# F_BRIDGE.net
KiCad netlist of a schematic drawn in Altium Designer
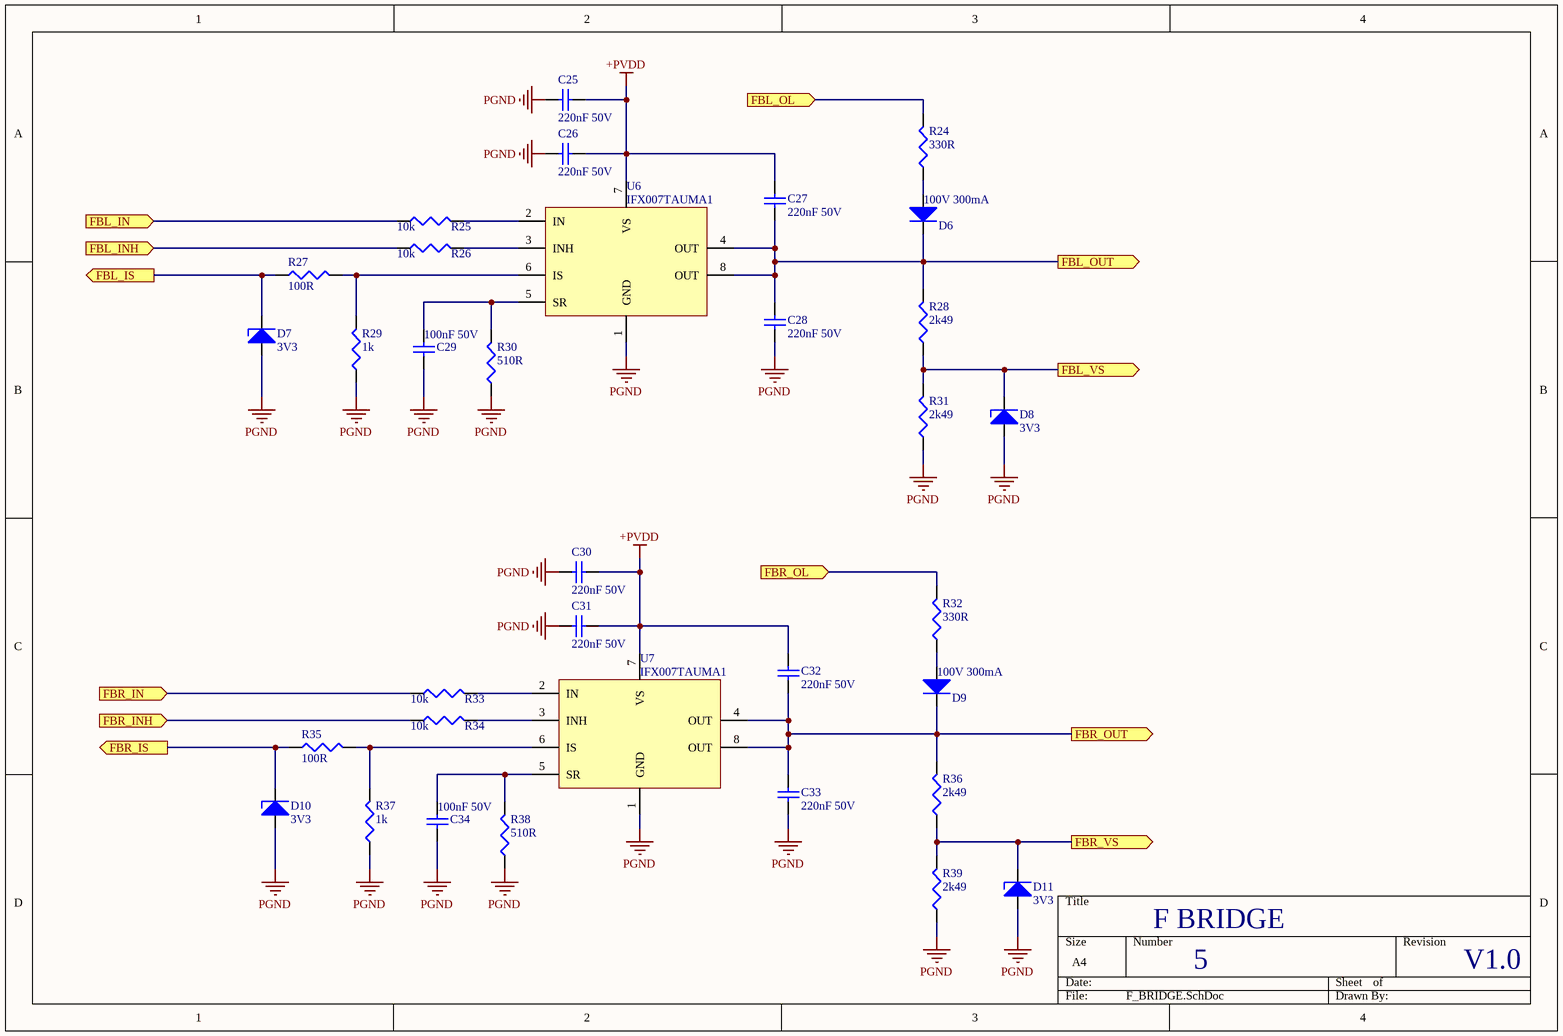
[diagram p0: F_BRIDGE.SchDoc]

(export (version "E")
  (design (tool "Eeschema 10.0.6"))
  (components
    (comp (ref "C25")
      (value "220nF 50V")
      (footprint "CAP1206")
      (description "CAP CER 0.22UF 50V X7R 1206")
      (libsource (lib "SMALL_BCM") (part "CAP1206_220nF"))
    )
    (comp (ref "C26")
      (value "220nF 50V")
      (footprint "CAP1206")
      (description "CAP CER 0.22UF 50V X7R 1206")
      (libsource (lib "SMALL_BCM") (part "CAP1206_220nF"))
    )
    (comp (ref "C27")
      (value "220nF 50V")
      (footprint "CAP1206")
      (description "CAP CER 0.22UF 50V X7R 1206")
      (libsource (lib "SMALL_BCM") (part "CAP1206_220nF"))
    )
    (comp (ref "C28")
      (value "220nF 50V")
      (footprint "CAP1206")
      (description "CAP CER 0.22UF 50V X7R 1206")
      (libsource (lib "SMALL_BCM") (part "CAP1206_220nF"))
    )
    (comp (ref "C29")
      (value "100nF 50V")
      (footprint "CAP0603")
      (description "CAP CER 0.1UF 50V X7R 0603")
      (libsource (lib "SMALL_BCM") (part "CAP0603_100nF"))
    )
    (comp (ref "C30")
      (value "220nF 50V")
      (footprint "CAP1206")
      (description "CAP CER 0.22UF 50V X7R 1206")
      (libsource (lib "SMALL_BCM") (part "CAP1206_220nF"))
    )
    (comp (ref "C31")
      (value "220nF 50V")
      (footprint "CAP1206")
      (description "CAP CER 0.22UF 50V X7R 1206")
      (libsource (lib "SMALL_BCM") (part "CAP1206_220nF"))
    )
    (comp (ref "C32")
      (value "220nF 50V")
      (footprint "CAP1206")
      (description "CAP CER 0.22UF 50V X7R 1206")
      (libsource (lib "SMALL_BCM") (part "CAP1206_220nF"))
    )
    (comp (ref "C33")
      (value "220nF 50V")
      (footprint "CAP1206")
      (description "CAP CER 0.22UF 50V X7R 1206")
      (libsource (lib "SMALL_BCM") (part "CAP1206_220nF"))
    )
    (comp (ref "C34")
      (value "100nF 50V")
      (footprint "CAP0603")
      (description "CAP CER 0.1UF 50V X7R 0603")
      (libsource (lib "SMALL_BCM") (part "CAP0603_100nF"))
    )
    (comp (ref "D6")
      (value "100V 300mA")
      (footprint "SOD123_1N4148W-7-F")
      (description "DIODE GEN PURP 100V 300MA SOD123")
      (libsource (lib "SMALL_BCM") (part "DIODE_1N4148W-7-F"))
    )
    (comp (ref "D7")
      (value "3V3")
      (footprint "SOD323")
      (description "DIODE ZENER 3.3V 300MW SOD323")
      (libsource (lib "SMALL_BCM") (part "ZENER_3V3_MM3Z3V3T1G"))
    )
    (comp (ref "D8")
      (value "3V3")
      (footprint "SOD323")
      (description "DIODE ZENER 3.3V 300MW SOD323")
      (libsource (lib "SMALL_BCM") (part "ZENER_3V3_MM3Z3V3T1G"))
    )
    (comp (ref "D9")
      (value "100V 300mA")
      (footprint "SOD123_1N4148W-7-F")
      (description "DIODE GEN PURP 100V 300MA SOD123")
      (libsource (lib "SMALL_BCM") (part "DIODE_1N4148W-7-F"))
    )
    (comp (ref "D10")
      (value "3V3")
      (footprint "SOD323")
      (description "DIODE ZENER 3.3V 300MW SOD323")
      (libsource (lib "SMALL_BCM") (part "ZENER_3V3_MM3Z3V3T1G"))
    )
    (comp (ref "D11")
      (value "3V3")
      (footprint "SOD323")
      (description "DIODE ZENER 3.3V 300MW SOD323")
      (libsource (lib "SMALL_BCM") (part "ZENER_3V3_MM3Z3V3T1G"))
    )
    (comp (ref "R24")
      (value "330R")
      (footprint "RES0603")
      (description "RES 330 OHM 1% 1/10W 0603")
      (libsource (lib "SMALL_BCM") (part "RES0603_330R"))
    )
    (comp (ref "R25")
      (value "10k")
      (footprint "RES0603")
      (description "RES SMD 10K OHM 5% 1/10W 0603")
      (libsource (lib "SMALL_BCM") (part "RES0603_10k"))
    )
    (comp (ref "R26")
      (value "10k")
      (footprint "RES0603")
      (description "RES SMD 10K OHM 5% 1/10W 0603")
      (libsource (lib "SMALL_BCM") (part "RES0603_10k"))
    )
    (comp (ref "R27")
      (value "100R")
      (footprint "RES0603")
      (description "RES SMD 100R OHM 1% 1/10W 0603")
      (libsource (lib "SMALL_BCM") (part "RES0603_100R"))
    )
    (comp (ref "R28")
      (value "2k49")
      (footprint "RES0603")
      (description "RES 2.49K OHM 1% 1/10W 0603")
      (libsource (lib "SMALL_BCM") (part "RES0603_2k49"))
    )
    (comp (ref "R29")
      (value "1k")
      (footprint "RES0603")
      (description "RES SMD 1K OHM 1% 1/10W 0603")
      (libsource (lib "SMALL_BCM") (part "RES0603_1k"))
    )
    (comp (ref "R30")
      (value "510R")
      (footprint "RES0603")
      (description "RES 510R OHM 1% 1/10W 0603")
      (libsource (lib "SMALL_BCM") (part "RES0603_510R"))
    )
    (comp (ref "R31")
      (value "2k49")
      (footprint "RES0603")
      (description "RES 2.49K OHM 1% 1/10W 0603")
      (libsource (lib "SMALL_BCM") (part "RES0603_2k49"))
    )
    (comp (ref "R32")
      (value "330R")
      (footprint "RES0603")
      (description "RES 330 OHM 1% 1/10W 0603")
      (libsource (lib "SMALL_BCM") (part "RES0603_330R"))
    )
    (comp (ref "R33")
      (value "10k")
      (footprint "RES0603")
      (description "RES SMD 10K OHM 5% 1/10W 0603")
      (libsource (lib "SMALL_BCM") (part "RES0603_10k"))
    )
    (comp (ref "R34")
      (value "10k")
      (footprint "RES0603")
      (description "RES SMD 10K OHM 5% 1/10W 0603")
      (libsource (lib "SMALL_BCM") (part "RES0603_10k"))
    )
    (comp (ref "R35")
      (value "100R")
      (footprint "RES0603")
      (description "RES SMD 100R OHM 1% 1/10W 0603")
      (libsource (lib "SMALL_BCM") (part "RES0603_100R"))
    )
    (comp (ref "R36")
      (value "2k49")
      (footprint "RES0603")
      (description "RES 2.49K OHM 1% 1/10W 0603")
      (libsource (lib "SMALL_BCM") (part "RES0603_2k49"))
    )
    (comp (ref "R37")
      (value "1k")
      (footprint "RES0603")
      (description "RES SMD 1K OHM 1% 1/10W 0603")
      (libsource (lib "SMALL_BCM") (part "RES0603_1k"))
    )
    (comp (ref "R38")
      (value "510R")
      (footprint "RES0603")
      (description "RES 510R OHM 1% 1/10W 0603")
      (libsource (lib "SMALL_BCM") (part "RES0603_510R"))
    )
    (comp (ref "R39")
      (value "2k49")
      (footprint "RES0603")
      (description "RES 2.49K OHM 1% 1/10W 0603")
      (libsource (lib "SMALL_BCM") (part "RES0603_2k49"))
    )
    (comp (ref "U6")
      (value "55A")
      (footprint "TO-263-8")
      (description "IC HALF-BRIDGE DRVR 2 CH TO263")
      (fields (field (name "P/N") "IFX007TAUMA1"))
      (libsource (lib "SMALL_BCM") (part "HB_IFX007TAUMA1"))
    )
    (comp (ref "U7")
      (value "55A")
      (footprint "TO-263-8")
      (description "IC HALF-BRIDGE DRVR 2 CH TO263")
      (fields (field (name "P/N") "IFX007TAUMA1"))
      (libsource (lib "SMALL_BCM") (part "HB_IFX007TAUMA1"))
    )
  )
  (nets
    (net (code "1") (name "+PVDD") (class "Default")
      (node (ref "C25") (pin "2") (pinfunction "2_2") (pintype "passive"))
      (node (ref "C26") (pin "2") (pinfunction "2_2") (pintype "passive"))
      (node (ref "C27") (pin "1") (pinfunction "1_1") (pintype "passive"))
      (node (ref "C30") (pin "2") (pinfunction "2_2") (pintype "passive"))
      (node (ref "C31") (pin "2") (pinfunction "2_2") (pintype "passive"))
      (node (ref "C32") (pin "1") (pinfunction "1_1") (pintype "passive"))
      (node (ref "U6") (pin "7") (pinfunction "VS_7") (pintype "power_in"))
      (node (ref "U7") (pin "7") (pinfunction "VS_7") (pintype "power_in"))
    )
    (net (code "2") (name "/FBL_IN") (class "Default")
      (node (ref "R25") (pin "1") (pinfunction "1_1") (pintype "passive"))
    )
    (net (code "3") (name "/FBL_INH") (class "Default")
      (node (ref "R26") (pin "1") (pinfunction "1_1") (pintype "passive"))
    )
    (net (code "4") (name "/FBL_IS") (class "Default")
      (node (ref "D7") (pin "1") (pinfunction "K_1") (pintype "passive"))
      (node (ref "R27") (pin "1") (pinfunction "1_1") (pintype "passive"))
    )
    (net (code "5") (name "/FBL_OL") (class "Default")
      (node (ref "R24") (pin "2") (pinfunction "2_2") (pintype "passive"))
    )
    (net (code "6") (name "/FBL_OUT") (class "Default")
      (node (ref "C27") (pin "2") (pinfunction "2_2") (pintype "passive"))
      (node (ref "C28") (pin "1") (pinfunction "1_1") (pintype "passive"))
      (node (ref "D6") (pin "2") (pinfunction "K_2") (pintype "passive"))
      (node (ref "R28") (pin "2") (pinfunction "2_2") (pintype "passive"))
      (node (ref "U6") (pin "4") (pinfunction "OUT_4") (pintype "passive"))
      (node (ref "U6") (pin "8") (pinfunction "OUT_8") (pintype "passive"))
    )
    (net (code "7") (name "/FBL_VS") (class "Default")
      (node (ref "D8") (pin "1") (pinfunction "K_1") (pintype "passive"))
      (node (ref "R28") (pin "1") (pinfunction "1_1") (pintype "passive"))
      (node (ref "R31") (pin "2") (pinfunction "2_2") (pintype "passive"))
    )
    (net (code "8") (name "/FBR_IN") (class "Default")
      (node (ref "R33") (pin "1") (pinfunction "1_1") (pintype "passive"))
    )
    (net (code "9") (name "/FBR_INH") (class "Default")
      (node (ref "R34") (pin "1") (pinfunction "1_1") (pintype "passive"))
    )
    (net (code "10") (name "/FBR_IS") (class "Default")
      (node (ref "D10") (pin "1") (pinfunction "K_1") (pintype "passive"))
      (node (ref "R35") (pin "1") (pinfunction "1_1") (pintype "passive"))
    )
    (net (code "11") (name "/FBR_OL") (class "Default")
      (node (ref "R32") (pin "2") (pinfunction "2_2") (pintype "passive"))
    )
    (net (code "12") (name "/FBR_OUT") (class "Default")
      (node (ref "C32") (pin "2") (pinfunction "2_2") (pintype "passive"))
      (node (ref "C33") (pin "1") (pinfunction "1_1") (pintype "passive"))
      (node (ref "D9") (pin "2") (pinfunction "K_2") (pintype "passive"))
      (node (ref "R36") (pin "2") (pinfunction "2_2") (pintype "passive"))
      (node (ref "U7") (pin "4") (pinfunction "OUT_4") (pintype "passive"))
      (node (ref "U7") (pin "8") (pinfunction "OUT_8") (pintype "passive"))
    )
    (net (code "13") (name "/FBR_VS") (class "Default")
      (node (ref "D11") (pin "1") (pinfunction "K_1") (pintype "passive"))
      (node (ref "R36") (pin "1") (pinfunction "1_1") (pintype "passive"))
      (node (ref "R39") (pin "2") (pinfunction "2_2") (pintype "passive"))
    )
    (net (code "14") (name "Net-(D6-A)") (class "Default")
      (node (ref "D6") (pin "1") (pinfunction "A_1") (pintype "passive"))
      (node (ref "R24") (pin "1") (pinfunction "1_1") (pintype "passive"))
    )
    (net (code "15") (name "Net-(D9-A)") (class "Default")
      (node (ref "D9") (pin "1") (pinfunction "A_1") (pintype "passive"))
      (node (ref "R32") (pin "1") (pinfunction "1_1") (pintype "passive"))
    )
    (net (code "16") (name "Net-(U6-IN)") (class "Default")
      (node (ref "R25") (pin "2") (pinfunction "2_2") (pintype "passive"))
      (node (ref "U6") (pin "2") (pinfunction "IN_2") (pintype "passive"))
    )
    (net (code "17") (name "Net-(U6-INH)") (class "Default")
      (node (ref "R26") (pin "2") (pinfunction "2_2") (pintype "passive"))
      (node (ref "U6") (pin "3") (pinfunction "INH_3") (pintype "passive"))
    )
    (net (code "18") (name "Net-(U6-IS)") (class "Default")
      (node (ref "R27") (pin "2") (pinfunction "2_2") (pintype "passive"))
      (node (ref "R29") (pin "2") (pinfunction "2_2") (pintype "passive"))
      (node (ref "U6") (pin "6") (pinfunction "IS_6") (pintype "passive"))
    )
    (net (code "19") (name "Net-(U6-SR)") (class "Default")
      (node (ref "C29") (pin "2") (pinfunction "2_2") (pintype "passive"))
      (node (ref "R30") (pin "2") (pinfunction "2_2") (pintype "passive"))
      (node (ref "U6") (pin "5") (pinfunction "SR_5") (pintype "passive"))
    )
    (net (code "20") (name "Net-(U7-IN)") (class "Default")
      (node (ref "R33") (pin "2") (pinfunction "2_2") (pintype "passive"))
      (node (ref "U7") (pin "2") (pinfunction "IN_2") (pintype "passive"))
    )
    (net (code "21") (name "Net-(U7-INH)") (class "Default")
      (node (ref "R34") (pin "2") (pinfunction "2_2") (pintype "passive"))
      (node (ref "U7") (pin "3") (pinfunction "INH_3") (pintype "passive"))
    )
    (net (code "22") (name "Net-(U7-IS)") (class "Default")
      (node (ref "R35") (pin "2") (pinfunction "2_2") (pintype "passive"))
      (node (ref "R37") (pin "2") (pinfunction "2_2") (pintype "passive"))
      (node (ref "U7") (pin "6") (pinfunction "IS_6") (pintype "passive"))
    )
    (net (code "23") (name "Net-(U7-SR)") (class "Default")
      (node (ref "C34") (pin "2") (pinfunction "2_2") (pintype "passive"))
      (node (ref "R38") (pin "2") (pinfunction "2_2") (pintype "passive"))
      (node (ref "U7") (pin "5") (pinfunction "SR_5") (pintype "passive"))
    )
    (net (code "24") (name "PGND") (class "Default")
      (node (ref "C25") (pin "1") (pinfunction "1_1") (pintype "passive"))
      (node (ref "C26") (pin "1") (pinfunction "1_1") (pintype "passive"))
      (node (ref "C28") (pin "2") (pinfunction "2_2") (pintype "passive"))
      (node (ref "C29") (pin "1") (pinfunction "1_1") (pintype "passive"))
      (node (ref "C30") (pin "1") (pinfunction "1_1") (pintype "passive"))
      (node (ref "C31") (pin "1") (pinfunction "1_1") (pintype "passive"))
      (node (ref "C33") (pin "2") (pinfunction "2_2") (pintype "passive"))
      (node (ref "C34") (pin "1") (pinfunction "1_1") (pintype "passive"))
      (node (ref "D10") (pin "2") (pinfunction "A_2") (pintype "passive"))
      (node (ref "D11") (pin "2") (pinfunction "A_2") (pintype "passive"))
      (node (ref "D7") (pin "2") (pinfunction "A_2") (pintype "passive"))
      (node (ref "D8") (pin "2") (pinfunction "A_2") (pintype "passive"))
      (node (ref "R29") (pin "1") (pinfunction "1_1") (pintype "passive"))
      (node (ref "R30") (pin "1") (pinfunction "1_1") (pintype "passive"))
      (node (ref "R31") (pin "1") (pinfunction "1_1") (pintype "passive"))
      (node (ref "R37") (pin "1") (pinfunction "1_1") (pintype "passive"))
      (node (ref "R38") (pin "1") (pinfunction "1_1") (pintype "passive"))
      (node (ref "R39") (pin "1") (pinfunction "1_1") (pintype "passive"))
      (node (ref "U6") (pin "1") (pinfunction "GND_1") (pintype "power_in"))
      (node (ref "U7") (pin "1") (pinfunction "GND_1") (pintype "power_in"))
    )
  )
)
